# Yusynth_VCA_-_Schematic.net
KiCad netlist of a schematic drawn in Altium Designer
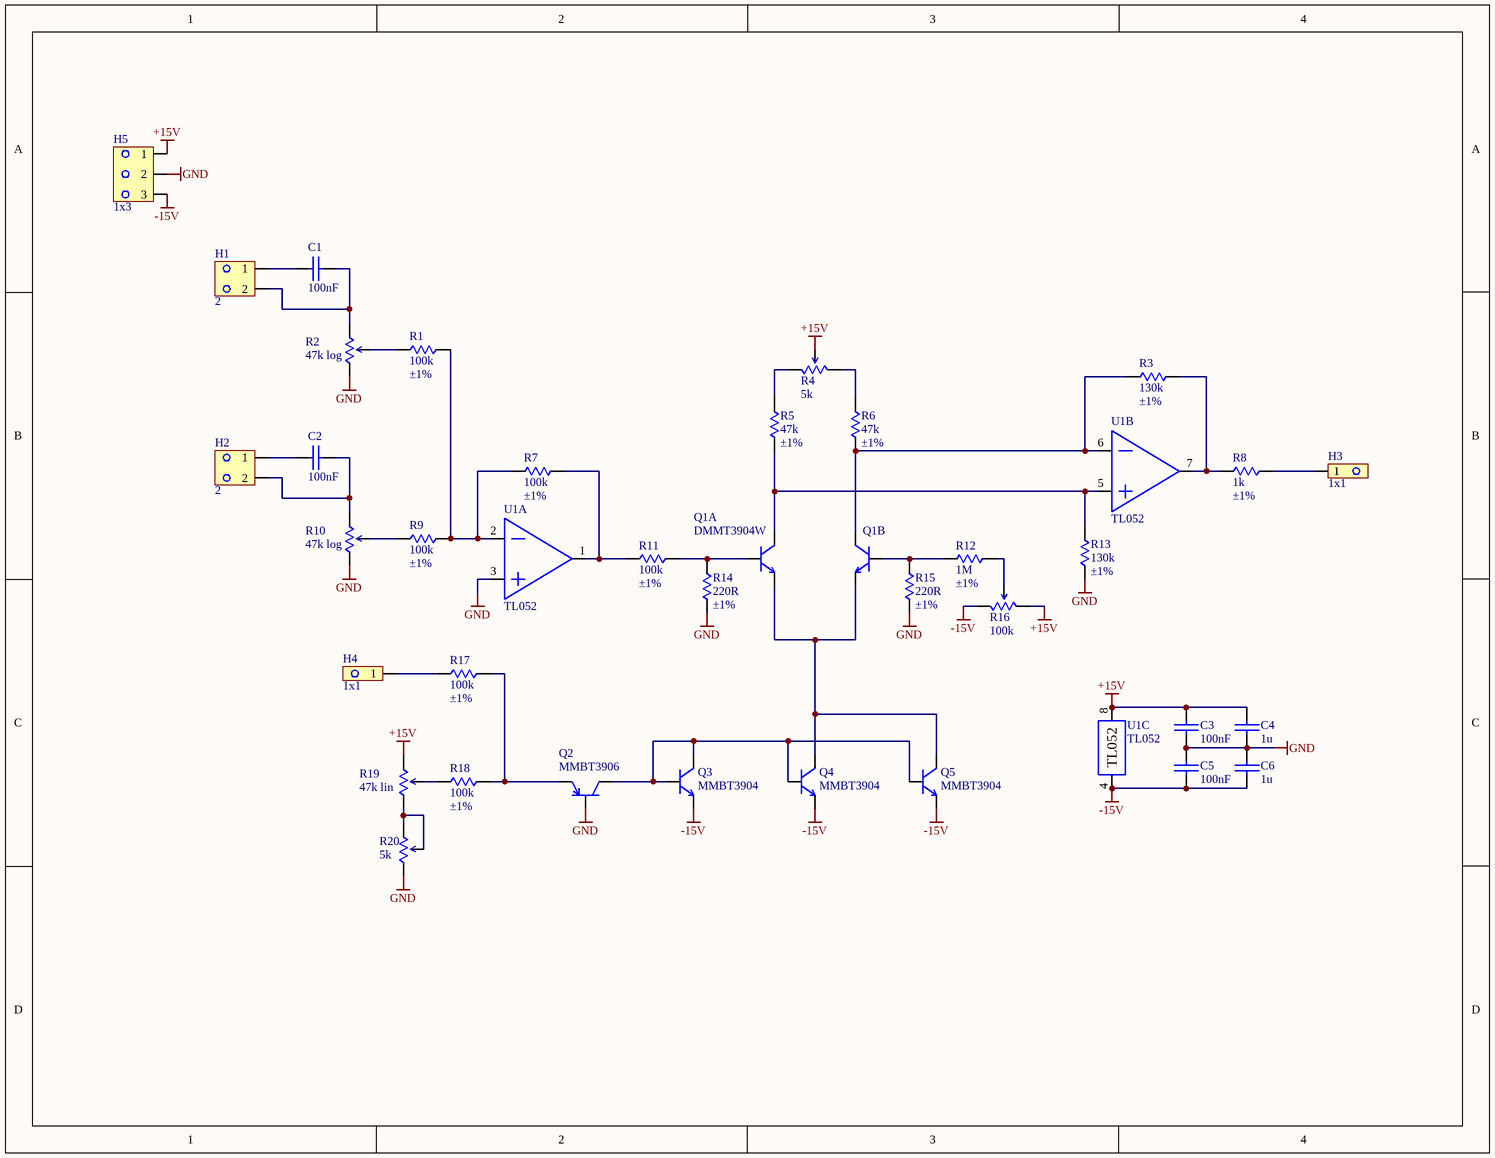
[diagram p0: Yusynth VCA - Schematic.SchDoc]

(export (version "E")
  (design (tool "Eeschema 10.0.6"))
  (components
    (comp (ref "C1")
      (value "100nF")
      (footprint "JEDEC - 0603 - cap")
      (description "CAP CER 0.1UF 50V X7R 0603")
      (fields (field (name "MFG") "Yageo") (field (name "VOLTAGE") "50V"))
      (libsource (lib "Adam home") (part "c - 100nF"))
    )
    (comp (ref "C2")
      (value "100nF")
      (footprint "JEDEC - 0603 - cap")
      (description "CAP CER 0.1UF 50V X7R 0603")
      (fields (field (name "MFG") "Yageo") (field (name "VOLTAGE") "50V"))
      (libsource (lib "Adam home") (part "c - 100nF"))
    )
    (comp (ref "C3")
      (value "100nF")
      (footprint "JEDEC - 0603 - cap")
      (description "CAP CER 0.1UF 50V X7R 0603")
      (fields (field (name "MFG") "Yageo") (field (name "VOLTAGE") "50V"))
      (libsource (lib "Adam home") (part "c - 100nF"))
    )
    (comp (ref "C4")
      (value "1u")
      (footprint "JEDEC - 0603 - cap")
      (description "CAP CER 1UF 50V X5R 0603")
      (fields (field (name "MFG") "Yageo") (field (name "VOLTAGE") "50V"))
      (libsource (lib "Adam home") (part "c - 1uF 50V 0603"))
    )
    (comp (ref "C5")
      (value "100nF")
      (footprint "JEDEC - 0603 - cap")
      (description "CAP CER 0.1UF 50V X7R 0603")
      (fields (field (name "MFG") "Yageo") (field (name "VOLTAGE") "50V"))
      (libsource (lib "Adam home") (part "c - 100nF"))
    )
    (comp (ref "C6")
      (value "1u")
      (footprint "JEDEC - 0603 - cap")
      (description "CAP CER 1UF 50V X5R 0603")
      (fields (field (name "MFG") "Yageo") (field (name "VOLTAGE") "50V"))
      (libsource (lib "Adam home") (part "c - 1uF 50V 0603"))
    )
    (comp (ref "H1")
      (value "2")
      (footprint "H - 100MIL - 1x2")
      (libsource (lib "Adam home") (part "Header - 1x2"))
    )
    (comp (ref "H2")
      (value "2")
      (footprint "H - 100MIL - 1x2")
      (libsource (lib "Adam home") (part "Header - 1x2"))
    )
    (comp (ref "H3")
      (value "1x1")
      (footprint "H - 100MIL - 1x1")
      (libsource (lib "Adam home") (part "Header - 1x1"))
    )
    (comp (ref "H4")
      (value "1x1")
      (footprint "H - 100MIL - 1x1")
      (libsource (lib "") (part "Header - 1x1_1"))
    )
    (comp (ref "H5")
      (value "1x3")
      (footprint "H - 100MIL - 1x3")
      (libsource (lib "Adam home") (part "Header - 1x3"))
    )
    (comp (ref "Q1")
      (value "DMMT3904W")
      (footprint "Diodes Inc - SOT363")
      (description "TRANS 2NPN 40V 0.2A SOT363")
      (fields (field (name "MFG") "Diodes Inc."))
      (libsource (lib "Adam home") (part "tran - matched npn - DMMT3904W"))
    )
    (comp (ref "Q2")
      (value "MMBT3906")
      (footprint "SOT 23")
      (description "TRANS PNP 40V 0.2A SOT23")
      (fields (field (name "MFG") "Micro Commercial Co"))
      (libsource (lib "Adam home") (part "tran - PNP - MMBT3906"))
    )
    (comp (ref "Q3")
      (value "MMBT3904")
      (footprint "SOT 23")
      (description "TRANS NPN 40V 0.2A SOT23")
      (fields (field (name "MFG") "Micro Commercial"))
      (libsource (lib "Adam home") (part "tran - NPN - MMBT3904"))
    )
    (comp (ref "Q4")
      (value "MMBT3904")
      (footprint "SOT 23")
      (description "TRANS NPN 40V 0.2A SOT23")
      (fields (field (name "MFG") "Micro Commercial"))
      (libsource (lib "Adam home") (part "tran - NPN - MMBT3904"))
    )
    (comp (ref "Q5")
      (value "MMBT3904")
      (footprint "SOT 23")
      (description "TRANS NPN 40V 0.2A SOT23")
      (fields (field (name "MFG") "Micro Commercial"))
      (libsource (lib "Adam home") (part "tran - NPN - MMBT3904"))
    )
    (comp (ref "R1")
      (value "100k")
      (footprint "JEDEC - 0603")
      (description "RES SMD 100K OHM 1% 1/10W 0603")
      (fields (field (name "MFG") "Yageo") (field (name "TOLERANCE") "±1%"))
      (libsource (lib "Adam home") (part "R - 100k 1% 0603"))
    )
    (comp (ref "R2")
      (value "47k log")
      (footprint "H - 100MIL - 1x3")
      (libsource (lib "Adam home") (part "g - pot 3"))
    )
    (comp (ref "R3")
      (value "130k")
      (footprint "JEDEC - 0603")
      (description "RES SMD 130K OHM 1% 1/10W 0603")
      (fields (field (name "MFG") "Yageo") (field (name "TOLERANCE") "±1%"))
      (libsource (lib "Adam home") (part "R - 130k 1% 0603"))
    )
    (comp (ref "R4")
      (value "5k")
      (footprint "POT - CTS - 262 Series")
      (description "TRIMMER 5K OHM 0.15W TH")
      (fields (field (name "MFG") "CTS Electrocomponents") (field (name "POWER") "0.15W"))
      (libsource (lib "Adam home") (part "pot - 262 - 5k"))
    )
    (comp (ref "R5")
      (value "47k")
      (footprint "JEDEC - 0603")
      (description "RES SMD 47K OHM 1% 1/10W 0603")
      (fields (field (name "MFG") "Yageo") (field (name "TOLERANCE") "±1%"))
      (libsource (lib "Adam home") (part "R - 47k 1% 0603"))
    )
    (comp (ref "R6")
      (value "47k")
      (footprint "JEDEC - 0603")
      (description "RES SMD 47K OHM 1% 1/10W 0603")
      (fields (field (name "MFG") "Yageo") (field (name "TOLERANCE") "±1%"))
      (libsource (lib "Adam home") (part "R - 47k 1% 0603"))
    )
    (comp (ref "R7")
      (value "100k")
      (footprint "JEDEC - 0603")
      (description "RES SMD 100K OHM 1% 1/10W 0603")
      (fields (field (name "MFG") "Yageo") (field (name "TOLERANCE") "±1%"))
      (libsource (lib "Adam home") (part "R - 100k 1% 0603"))
    )
    (comp (ref "R8")
      (value "1k")
      (footprint "JEDEC - 0603")
      (description "RES SMD 1K OHM 1% 1/10W 0603")
      (fields (field (name "MFG") "Yageo") (field (name "TOLERANCE") "±1%"))
      (libsource (lib "Adam home") (part "R - 1k 1% 0603"))
    )
    (comp (ref "R9")
      (value "100k")
      (footprint "JEDEC - 0603")
      (description "RES SMD 100K OHM 1% 1/10W 0603")
      (fields (field (name "MFG") "Yageo") (field (name "TOLERANCE") "±1%"))
      (libsource (lib "Adam home") (part "R - 100k 1% 0603"))
    )
    (comp (ref "R10")
      (value "47k log")
      (footprint "H - 100MIL - 1x3")
      (libsource (lib "Adam home") (part "g - pot 3"))
    )
    (comp (ref "R11")
      (value "100k")
      (footprint "JEDEC - 0603")
      (description "RES SMD 100K OHM 1% 1/10W 0603")
      (fields (field (name "MFG") "Yageo") (field (name "TOLERANCE") "±1%"))
      (libsource (lib "Adam home") (part "R - 100k 1% 0603"))
    )
    (comp (ref "R12")
      (value "1M")
      (footprint "JEDEC - 0603")
      (description "RES SMD 1M OHM 1% 1/10W 0603")
      (fields (field (name "MFG") "Yageo") (field (name "TOLERANCE") "±1%"))
      (libsource (lib "Adam home") (part "R - 1M 1% 0603"))
    )
    (comp (ref "R13")
      (value "130k")
      (footprint "JEDEC - 0603")
      (description "RES SMD 130K OHM 1% 1/10W 0603")
      (fields (field (name "MFG") "Yageo") (field (name "TOLERANCE") "±1%"))
      (libsource (lib "Adam home") (part "R - 130k 1% 0603"))
    )
    (comp (ref "R14")
      (value "220R")
      (footprint "JEDEC - 0603")
      (description "RES SMD 220 OHM 1% 1/10W 0603")
      (fields (field (name "MFG") "Yageo") (field (name "TOLERANCE") "±1%"))
      (libsource (lib "Adam home") (part "R - 220R 1% 0603"))
    )
    (comp (ref "R15")
      (value "220R")
      (footprint "JEDEC - 0603")
      (description "RES SMD 220 OHM 1% 1/10W 0603")
      (fields (field (name "MFG") "Yageo") (field (name "TOLERANCE") "±1%"))
      (libsource (lib "Adam home") (part "R - 220R 1% 0603"))
    )
    (comp (ref "R16")
      (value "100k")
      (footprint "POT - CTS - 262 Series")
      (description "TRIMMER 100K OHM 0.15W TH")
      (fields (field (name "MFG") "CTS Electrocomponents") (field (name "POWER") "0.15W"))
      (libsource (lib "Adam home") (part "pot - 262 - 100k"))
    )
    (comp (ref "R17")
      (value "100k")
      (footprint "JEDEC - 0603")
      (description "RES SMD 100K OHM 1% 1/10W 0603")
      (fields (field (name "MFG") "Yageo") (field (name "TOLERANCE") "±1%"))
      (libsource (lib "Adam home") (part "R - 100k 1% 0603"))
    )
    (comp (ref "R18")
      (value "100k")
      (footprint "JEDEC - 0603")
      (description "RES SMD 100K OHM 1% 1/10W 0603")
      (fields (field (name "MFG") "Yageo") (field (name "TOLERANCE") "±1%"))
      (libsource (lib "Adam home") (part "R - 100k 1% 0603"))
    )
    (comp (ref "R19")
      (value "47k lin")
      (footprint "H - 100MIL - 1x3")
      (libsource (lib "Adam home") (part "g - pot 3"))
    )
    (comp (ref "R20")
      (value "5k")
      (footprint "POT - CTS - 262 Series")
      (description "TRIMMER 5K OHM 0.15W TH")
      (fields (field (name "MFG") "CTS Electrocomponents") (field (name "POWER") "0.15W"))
      (libsource (lib "Adam home") (part "pot - 262 - 5k"))
    )
    (comp (ref "U1")
      (value "TL052")
      (footprint "TI - D (R-PDSO-G8)")
      (description "IC OPAMP JFET 3MHZ 8SOIC")
      (fields (field (name "MFG") "TI"))
      (libsource (lib "Adam home") (part "op amp - TL052"))
    )
  )
  (nets
    (net (code "1") (name "+15V") (class "Default")
      (node (ref "C3") (pin "2") (pintype "passive"))
      (node (ref "C4") (pin "1") (pintype "passive"))
      (node (ref "H5") (pin "1") (pinfunction "1_1") (pintype "passive"))
      (node (ref "R16") (pin "2") (pinfunction "2_2") (pintype "passive"))
      (node (ref "R19") (pin "3") (pinfunction "3_3") (pintype "passive"))
      (node (ref "R4") (pin "3") (pinfunction "3_3") (pintype "passive"))
      (node (ref "U1") (pin "8") (pinfunction "8_8") (pintype "passive"))
    )
    (net (code "2") (name "-15V") (class "Default")
      (node (ref "C5") (pin "1") (pintype "passive"))
      (node (ref "C6") (pin "2") (pintype "passive"))
      (node (ref "H5") (pin "3") (pinfunction "3_3") (pintype "passive"))
      (node (ref "Q3") (pin "2") (pinfunction "2_2") (pintype "passive"))
      (node (ref "Q4") (pin "2") (pinfunction "2_2") (pintype "passive"))
      (node (ref "Q5") (pin "2") (pinfunction "2_2") (pintype "passive"))
      (node (ref "R16") (pin "1") (pinfunction "1_1") (pintype "passive"))
      (node (ref "U1") (pin "4") (pinfunction "4_4") (pintype "passive"))
    )
    (net (code "3") (name "GND") (class "Default")
      (node (ref "C3") (pin "1") (pintype "passive"))
      (node (ref "C4") (pin "2") (pintype "passive"))
      (node (ref "C5") (pin "2") (pintype "passive"))
      (node (ref "C6") (pin "1") (pintype "passive"))
      (node (ref "H5") (pin "2") (pinfunction "2_2") (pintype "passive"))
      (node (ref "Q2") (pin "1") (pinfunction "1_1") (pintype "passive"))
      (node (ref "R10") (pin "1") (pintype "passive"))
      (node (ref "R13") (pin "1") (pintype "passive"))
      (node (ref "R14") (pin "1") (pintype "passive"))
      (node (ref "R15") (pin "1") (pintype "passive"))
      (node (ref "R2") (pin "1") (pintype "passive"))
      (node (ref "R20") (pin "1") (pinfunction "1_1") (pintype "passive"))
      (node (ref "U1") (pin "3") (pinfunction "3_3") (pintype "passive"))
    )
    (net (code "4") (name "Net-(C1-Pad1)") (class "Default")
      (node (ref "C1") (pin "1") (pintype "passive"))
      (node (ref "H1") (pin "1") (pinfunction "1_1") (pintype "passive"))
    )
    (net (code "5") (name "Net-(C1-Pad2)") (class "Default")
      (node (ref "C1") (pin "2") (pintype "passive"))
      (node (ref "H1") (pin "2") (pinfunction "2_2") (pintype "passive"))
      (node (ref "R2") (pin "3") (pinfunction "3_3") (pintype "passive"))
    )
    (net (code "6") (name "Net-(C2-Pad1)") (class "Default")
      (node (ref "C2") (pin "1") (pintype "passive"))
      (node (ref "H2") (pin "1") (pinfunction "1_1") (pintype "passive"))
    )
    (net (code "7") (name "Net-(C2-Pad2)") (class "Default")
      (node (ref "C2") (pin "2") (pintype "passive"))
      (node (ref "H2") (pin "2") (pinfunction "2_2") (pintype "passive"))
      (node (ref "R10") (pin "3") (pinfunction "3_3") (pintype "passive"))
    )
    (net (code "8") (name "Net-(H3-Pad1)") (class "Default")
      (node (ref "H3") (pin "1") (pinfunction "1_1") (pintype "passive"))
      (node (ref "R8") (pin "2") (pintype "passive"))
    )
    (net (code "9") (name "Net-(H4-Pad1)") (class "Default")
      (node (ref "H4") (pin "1") (pinfunction "1_1") (pintype "passive"))
      (node (ref "R17") (pin "1") (pintype "passive"))
    )
    (net (code "10") (name "Net-(Q1-Pad1)") (class "Default")
      (node (ref "Q1") (pin "1") (pinfunction "1_1") (pintype "passive"))
      (node (ref "R11") (pin "2") (pintype "passive"))
      (node (ref "R14") (pin "2") (pintype "passive"))
    )
    (net (code "11") (name "Net-(Q1-Pad2)") (class "Default")
      (node (ref "Q1") (pin "2") (pinfunction "2_2") (pintype "passive"))
      (node (ref "R12") (pin "1") (pintype "passive"))
      (node (ref "R15") (pin "2") (pintype "passive"))
    )
    (net (code "12") (name "Net-(Q1-Pad3)") (class "Default")
      (node (ref "Q1") (pin "3") (pinfunction "3_3") (pintype "passive"))
      (node (ref "R3") (pin "2") (pintype "passive"))
      (node (ref "R6") (pin "1") (pintype "passive"))
      (node (ref "U1") (pin "6") (pinfunction "6_6") (pintype "passive"))
    )
    (net (code "13") (name "Net-(Q1-Pad4)") (class "Default")
      (node (ref "Q1") (pin "4") (pinfunction "4_4") (pintype "passive"))
      (node (ref "Q1") (pin "5") (pinfunction "5_5") (pintype "passive"))
      (node (ref "Q4") (pin "3") (pinfunction "3_3") (pintype "passive"))
      (node (ref "Q5") (pin "3") (pinfunction "3_3") (pintype "passive"))
    )
    (net (code "14") (name "Net-(Q1-Pad6)") (class "Default")
      (node (ref "Q1") (pin "6") (pinfunction "6_6") (pintype "passive"))
      (node (ref "R13") (pin "2") (pintype "passive"))
      (node (ref "R5") (pin "1") (pintype "passive"))
      (node (ref "U1") (pin "5") (pinfunction "5_5") (pintype "passive"))
    )
    (net (code "15") (name "Net-(Q2-Pad2)") (class "Default")
      (node (ref "Q2") (pin "2") (pinfunction "2_2") (pintype "passive"))
      (node (ref "R17") (pin "2") (pintype "passive"))
      (node (ref "R18") (pin "2") (pintype "passive"))
    )
    (net (code "16") (name "Net-(Q2-Pad3)") (class "Default")
      (node (ref "Q2") (pin "3") (pinfunction "3_3") (pintype "passive"))
      (node (ref "Q3") (pin "1") (pinfunction "1_1") (pintype "passive"))
      (node (ref "Q3") (pin "3") (pinfunction "3_3") (pintype "passive"))
      (node (ref "Q4") (pin "1") (pinfunction "1_1") (pintype "passive"))
      (node (ref "Q5") (pin "1") (pinfunction "1_1") (pintype "passive"))
    )
    (net (code "17") (name "Net-(R1-Pad1)") (class "Default")
      (node (ref "R1") (pin "1") (pintype "passive"))
      (node (ref "R2") (pin "2") (pinfunction "2_2") (pintype "passive"))
    )
    (net (code "18") (name "Net-(R1-Pad2)") (class "Default")
      (node (ref "R1") (pin "2") (pintype "passive"))
      (node (ref "R7") (pin "1") (pintype "passive"))
      (node (ref "R9") (pin "2") (pintype "passive"))
      (node (ref "U1") (pin "2") (pinfunction "2_2") (pintype "passive"))
    )
    (net (code "19") (name "Net-(R3-Pad1)") (class "Default")
      (node (ref "R3") (pin "1") (pintype "passive"))
      (node (ref "R8") (pin "1") (pintype "passive"))
      (node (ref "U1") (pin "7") (pinfunction "7_7") (pintype "passive"))
    )
    (net (code "20") (name "Net-(R4-Pad1)") (class "Default")
      (node (ref "R4") (pin "1") (pinfunction "1_1") (pintype "passive"))
      (node (ref "R5") (pin "2") (pintype "passive"))
    )
    (net (code "21") (name "Net-(R4-Pad2)") (class "Default")
      (node (ref "R4") (pin "2") (pinfunction "2_2") (pintype "passive"))
      (node (ref "R6") (pin "2") (pintype "passive"))
    )
    (net (code "22") (name "Net-(R10-Pad2)") (class "Default")
      (node (ref "R10") (pin "2") (pinfunction "2_2") (pintype "passive"))
      (node (ref "R9") (pin "1") (pintype "passive"))
    )
    (net (code "23") (name "Net-(R11-Pad1)") (class "Default")
      (node (ref "R11") (pin "1") (pintype "passive"))
      (node (ref "R7") (pin "2") (pintype "passive"))
      (node (ref "U1") (pin "1") (pinfunction "1_1") (pintype "passive"))
    )
    (net (code "24") (name "Net-(R12-Pad2)") (class "Default")
      (node (ref "R12") (pin "2") (pintype "passive"))
      (node (ref "R16") (pin "3") (pinfunction "3_3") (pintype "passive"))
    )
    (net (code "25") (name "Net-(R18-Pad1)") (class "Default")
      (node (ref "R18") (pin "1") (pintype "passive"))
      (node (ref "R19") (pin "2") (pinfunction "2_2") (pintype "passive"))
    )
    (net (code "26") (name "Net-(R19-Pad1)") (class "Default")
      (node (ref "R19") (pin "1") (pintype "passive"))
      (node (ref "R20") (pin "2") (pinfunction "2_2") (pintype "passive"))
      (node (ref "R20") (pin "3") (pinfunction "3_3") (pintype "passive"))
    )
  )
)
